# daq.net
KiCad netlist of a schematic drawn in EAGLE
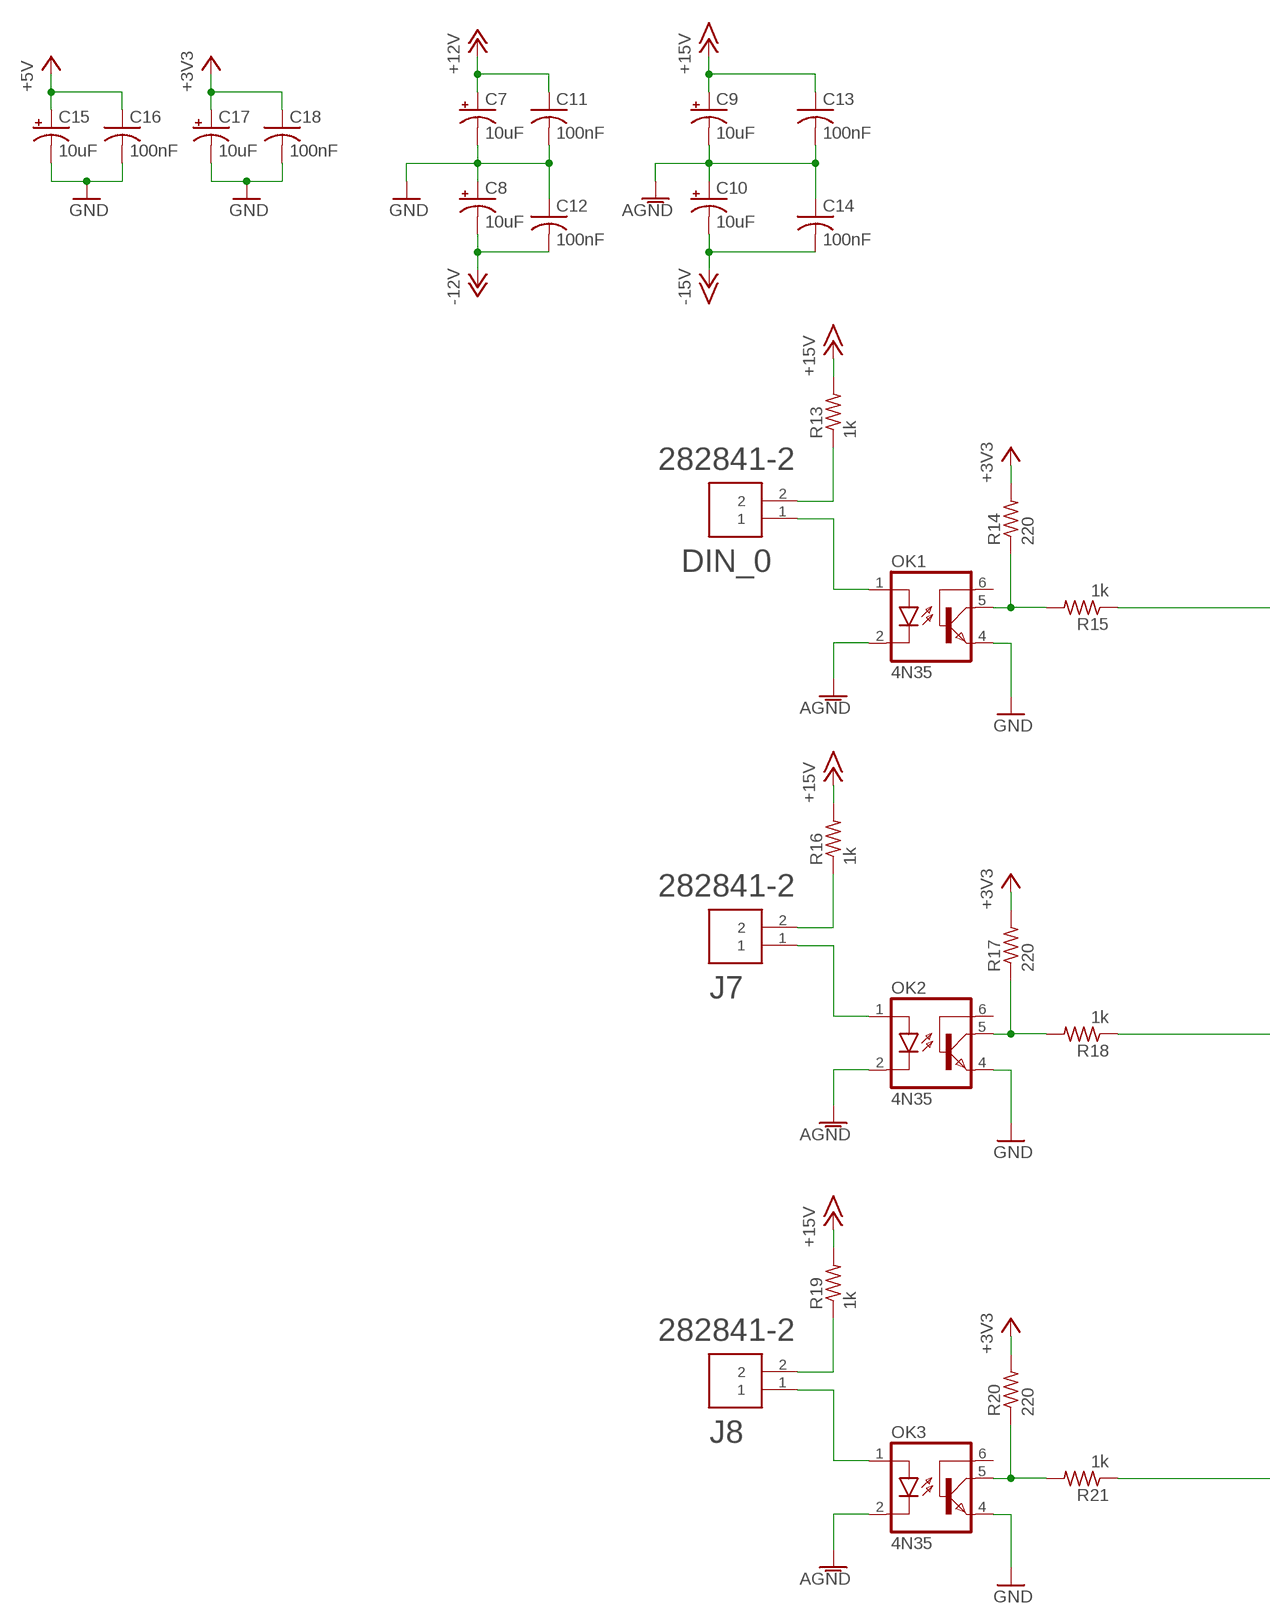
[diagram p0: schematic, sheet 1, part 1 of 2]
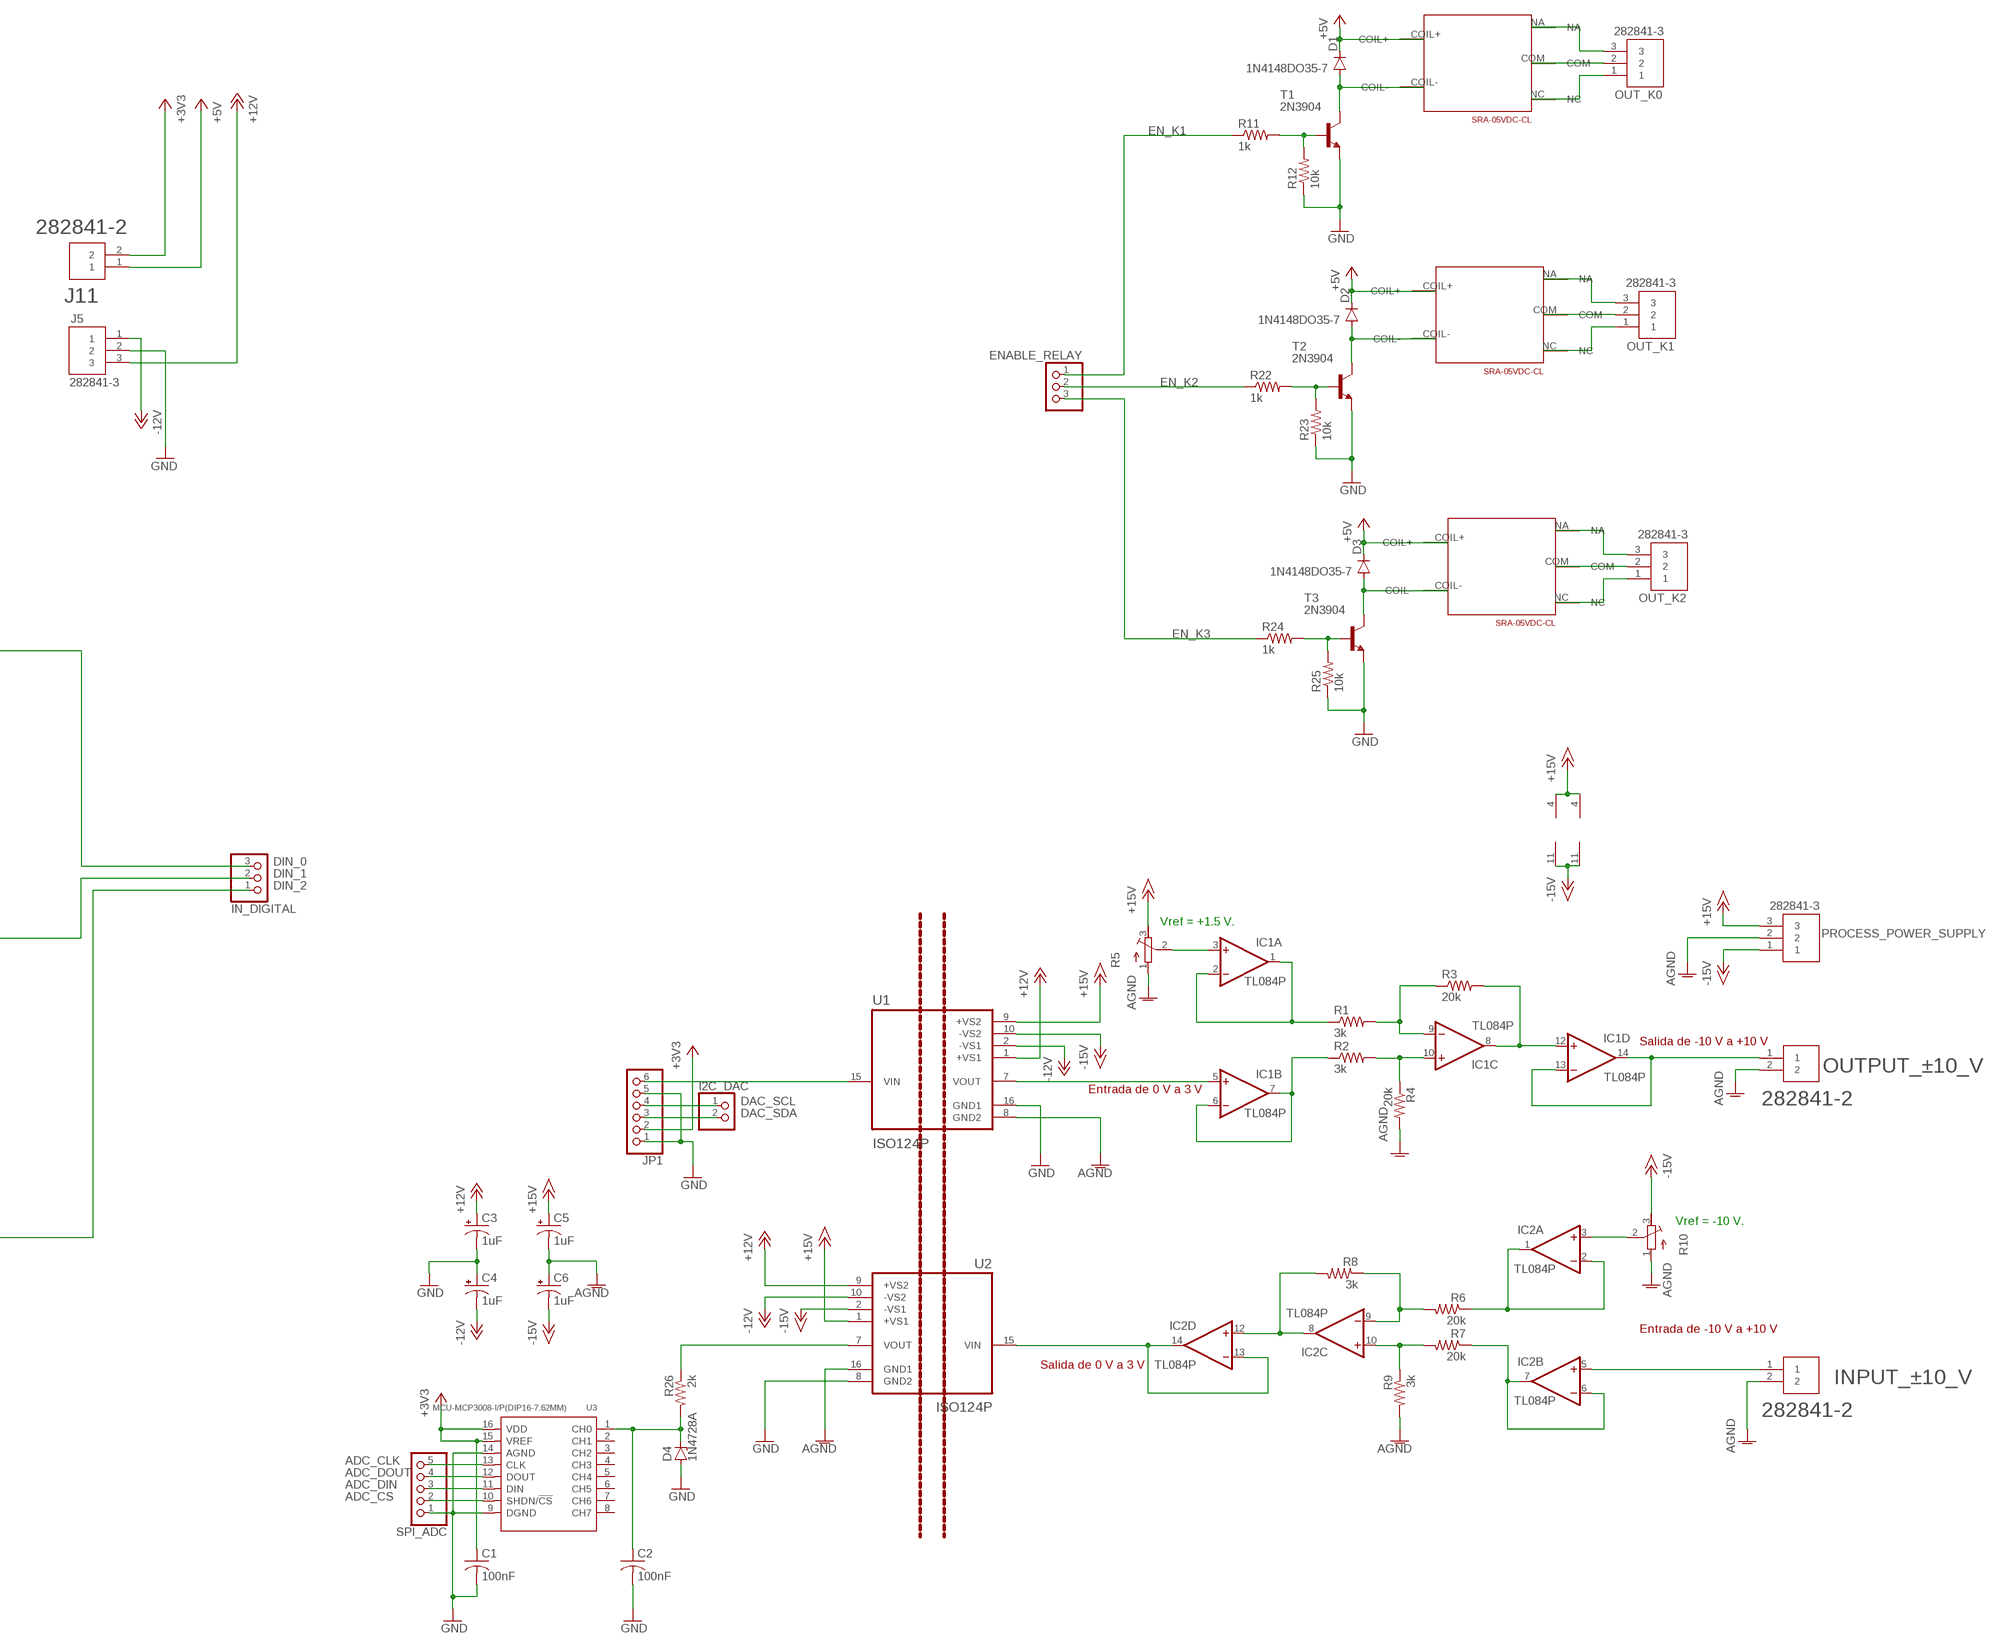
[diagram p1: schematic, sheet 1, part 2 of 2]

(export (version "E")
  (design (tool "Eeschema 10.0.6"))
  (components
    (comp (ref "C1")
      (value "100nF")
      (footprint "eagle-import:C025-025X050")
      (libsource (lib "eagle-import") (part "C-US025-025X050"))
    )
    (comp (ref "C2")
      (value "100nF")
      (footprint "eagle-import:C025-025X050")
      (libsource (lib "eagle-import") (part "C-US025-025X050"))
    )
    (comp (ref "C3")
      (value "1uF")
      (footprint "eagle-import:E2-5")
      (libsource (lib "eagle-import") (part "CPOL-USE2-5"))
    )
    (comp (ref "C4")
      (value "1uF")
      (footprint "eagle-import:E2-5")
      (libsource (lib "eagle-import") (part "CPOL-USE2-5"))
    )
    (comp (ref "C5")
      (value "1uF")
      (footprint "eagle-import:E2-5")
      (libsource (lib "eagle-import") (part "CPOL-USE2-5"))
    )
    (comp (ref "C6")
      (value "1uF")
      (footprint "eagle-import:E2-5")
      (libsource (lib "eagle-import") (part "CPOL-USE2-5"))
    )
    (comp (ref "C7")
      (value "10uF")
      (footprint "eagle-import:E2-5")
      (libsource (lib "eagle-import") (part "CPOL-USE2-5"))
    )
    (comp (ref "C8")
      (value "10uF")
      (footprint "eagle-import:E2-5")
      (libsource (lib "eagle-import") (part "CPOL-USE2-5"))
    )
    (comp (ref "C9")
      (value "10uF")
      (footprint "eagle-import:E2-5")
      (libsource (lib "eagle-import") (part "CPOL-USE2-5"))
    )
    (comp (ref "C10")
      (value "10uF")
      (footprint "eagle-import:E2-5")
      (libsource (lib "eagle-import") (part "CPOL-USE2-5"))
    )
    (comp (ref "C11")
      (value "100nF")
      (footprint "eagle-import:C025-025X050")
      (libsource (lib "eagle-import") (part "C-US025-025X050"))
    )
    (comp (ref "C12")
      (value "100nF")
      (footprint "eagle-import:C025-025X050")
      (libsource (lib "eagle-import") (part "C-US025-025X050"))
    )
    (comp (ref "C13")
      (value "100nF")
      (footprint "eagle-import:C025-025X050")
      (libsource (lib "eagle-import") (part "C-US025-025X050"))
    )
    (comp (ref "C14")
      (value "100nF")
      (footprint "eagle-import:C025-025X050")
      (libsource (lib "eagle-import") (part "C-US025-025X050"))
    )
    (comp (ref "C15")
      (value "10uF")
      (footprint "eagle-import:E2-5")
      (libsource (lib "eagle-import") (part "CPOL-USE2-5"))
    )
    (comp (ref "C16")
      (value "100nF")
      (footprint "eagle-import:C025-025X050")
      (libsource (lib "eagle-import") (part "C-US025-025X050"))
    )
    (comp (ref "C17")
      (value "10uF")
      (footprint "eagle-import:E2-5")
      (libsource (lib "eagle-import") (part "CPOL-USE2-5"))
    )
    (comp (ref "C18")
      (value "100nF")
      (footprint "eagle-import:C025-025X050")
      (libsource (lib "eagle-import") (part "C-US025-025X050"))
    )
    (comp (ref "D1")
      (value "1N4148DO35-7")
      (footprint "eagle-import:DO35-7")
      (libsource (lib "eagle-import") (part "1N4148DO35-7"))
    )
    (comp (ref "D2")
      (value "1N4148DO35-7")
      (footprint "eagle-import:DO35-7")
      (libsource (lib "eagle-import") (part "1N4148DO35-7"))
    )
    (comp (ref "D3")
      (value "1N4148DO35-7")
      (footprint "eagle-import:DO35-7")
      (libsource (lib "eagle-import") (part "1N4148DO35-7"))
    )
    (comp (ref "D4")
      (value "1N4728A")
      (footprint "eagle-import:DO41Z10")
      (libsource (lib "eagle-import") (part "ZENER-DIODEDO41Z10"))
    )
    (comp (ref "DIN_0")
      (value "282841-2")
      (footprint "eagle-import:TE_282841-2")
      (fields (field (name "MF") "TE Connectivity"))
      (libsource (lib "eagle-import") (part "282841-2"))
    )
    (comp (ref "ENABLE_RELAY")
      (value "PINHD-1X3")
      (footprint "eagle-import:1X03")
      (libsource (lib "eagle-import") (part "PINHD-1X3"))
    )
    (comp (ref "I2C_DAC")
      (value "PINHD-1X2")
      (footprint "eagle-import:1X02")
      (libsource (lib "eagle-import") (part "PINHD-1X2"))
    )
    (comp (ref "IC1")
      (value "TL084P")
      (footprint "eagle-import:DIL14")
      (libsource (lib "eagle-import") (part "TL084P"))
    )
    (comp (ref "IC2")
      (value "TL084P")
      (footprint "eagle-import:DIL14")
      (libsource (lib "eagle-import") (part "TL084P"))
    )
    (comp (ref "INPUT_±10_V")
      (value "282841-2")
      (footprint "eagle-import:TE_282841-2")
      (fields (field (name "MF") "TE Connectivity"))
      (libsource (lib "eagle-import") (part "282841-2"))
    )
    (comp (ref "IN_DIGITAL")
      (value "PINHD-1X3")
      (footprint "eagle-import:1X03")
      (libsource (lib "eagle-import") (part "PINHD-1X3"))
    )
    (comp (ref "J5")
      (value "282841-3")
      (footprint "eagle-import:TE_282841-3")
      (fields (field (name "MF") "TE Connectivity"))
      (libsource (lib "eagle-import") (part "282841-3"))
    )
    (comp (ref "J7")
      (value "282841-2")
      (footprint "eagle-import:TE_282841-2")
      (fields (field (name "MF") "TE Connectivity"))
      (libsource (lib "eagle-import") (part "282841-2"))
    )
    (comp (ref "J8")
      (value "282841-2")
      (footprint "eagle-import:TE_282841-2")
      (fields (field (name "MF") "TE Connectivity"))
      (libsource (lib "eagle-import") (part "282841-2"))
    )
    (comp (ref "J11")
      (value "282841-2")
      (footprint "eagle-import:TE_282841-2")
      (fields (field (name "MF") "TE Connectivity"))
      (libsource (lib "eagle-import") (part "282841-2"))
    )
    (comp (ref "JP1")
      (value "PINHD-1X6")
      (footprint "eagle-import:1X06")
      (libsource (lib "eagle-import") (part "PINHD-1X6"))
    )
    (comp (ref "OK1")
      (value "4N35")
      (footprint "eagle-import:DIL06")
      (fields (field (name "MF") "FAIRCHILD SEMICONDUCTOR"))
      (libsource (lib "eagle-import") (part "4N35"))
    )
    (comp (ref "OK2")
      (value "4N35")
      (footprint "eagle-import:DIL06")
      (fields (field (name "MF") "FAIRCHILD SEMICONDUCTOR"))
      (libsource (lib "eagle-import") (part "4N35"))
    )
    (comp (ref "OK3")
      (value "4N35")
      (footprint "eagle-import:DIL06")
      (fields (field (name "MF") "FAIRCHILD SEMICONDUCTOR"))
      (libsource (lib "eagle-import") (part "4N35"))
    )
    (comp (ref "OUTPUT_±10_V")
      (value "282841-2")
      (footprint "eagle-import:TE_282841-2")
      (fields (field (name "MF") "TE Connectivity"))
      (libsource (lib "eagle-import") (part "282841-2"))
    )
    (comp (ref "OUT_K0")
      (value "282841-3")
      (footprint "eagle-import:TE_282841-3")
      (fields (field (name "MF") "TE Connectivity"))
      (libsource (lib "eagle-import") (part "282841-3"))
    )
    (comp (ref "OUT_K1")
      (value "282841-3")
      (footprint "eagle-import:TE_282841-3")
      (fields (field (name "MF") "TE Connectivity"))
      (libsource (lib "eagle-import") (part "282841-3"))
    )
    (comp (ref "OUT_K2")
      (value "282841-3")
      (footprint "eagle-import:TE_282841-3")
      (fields (field (name "MF") "TE Connectivity"))
      (libsource (lib "eagle-import") (part "282841-3"))
    )
    (comp (ref "PROCESS_POWER_SUPPLY")
      (value "282841-3")
      (footprint "eagle-import:TE_282841-3")
      (fields (field (name "MF") "TE Connectivity"))
      (libsource (lib "eagle-import") (part "282841-3"))
    )
    (comp (ref "R1")
      (value "3k")
      (footprint "eagle-import:0207_10")
      (libsource (lib "eagle-import") (part "R-US_0207/10"))
    )
    (comp (ref "R2")
      (value "3k")
      (footprint "eagle-import:0207_10")
      (libsource (lib "eagle-import") (part "R-US_0207/10"))
    )
    (comp (ref "R3")
      (value "20k")
      (footprint "eagle-import:0207_10")
      (libsource (lib "eagle-import") (part "R-US_0207/10"))
    )
    (comp (ref "R4")
      (value "20k")
      (footprint "eagle-import:0207_10")
      (libsource (lib "eagle-import") (part "R-US_0207/10"))
    )
    (comp (ref "R5")
      (value "R-TRIMM64W")
      (footprint "eagle-import:RTRIM64W")
      (libsource (lib "eagle-import") (part "R-TRIMM64W"))
    )
    (comp (ref "R6")
      (value "20k")
      (footprint "eagle-import:0207_10")
      (libsource (lib "eagle-import") (part "R-US_0207/10"))
    )
    (comp (ref "R7")
      (value "20k")
      (footprint "eagle-import:0207_10")
      (libsource (lib "eagle-import") (part "R-US_0207/10"))
    )
    (comp (ref "R8")
      (value "3k")
      (footprint "eagle-import:0207_10")
      (libsource (lib "eagle-import") (part "R-US_0207/10"))
    )
    (comp (ref "R9")
      (value "3k")
      (footprint "eagle-import:0207_10")
      (libsource (lib "eagle-import") (part "R-US_0207/10"))
    )
    (comp (ref "R10")
      (value "R-TRIMM64W")
      (footprint "eagle-import:RTRIM64W")
      (libsource (lib "eagle-import") (part "R-TRIMM64W"))
    )
    (comp (ref "R11")
      (value "1k")
      (footprint "eagle-import:0207_10")
      (libsource (lib "eagle-import") (part "R-US_0207/10"))
    )
    (comp (ref "R12")
      (value "10k")
      (footprint "eagle-import:0207_10")
      (libsource (lib "eagle-import") (part "R-US_0207/10"))
    )
    (comp (ref "R13")
      (value "1k")
      (footprint "eagle-import:0207_10")
      (libsource (lib "eagle-import") (part "R-US_0207/10"))
    )
    (comp (ref "R14")
      (value "220")
      (footprint "eagle-import:0207_10")
      (libsource (lib "eagle-import") (part "R-US_0207/10"))
    )
    (comp (ref "R15")
      (value "1k")
      (footprint "eagle-import:0207_10")
      (libsource (lib "eagle-import") (part "R-US_0207/10"))
    )
    (comp (ref "R16")
      (value "1k")
      (footprint "eagle-import:0207_10")
      (libsource (lib "eagle-import") (part "R-US_0207/10"))
    )
    (comp (ref "R17")
      (value "220")
      (footprint "eagle-import:0207_10")
      (libsource (lib "eagle-import") (part "R-US_0207/10"))
    )
    (comp (ref "R18")
      (value "1k")
      (footprint "eagle-import:0207_10")
      (libsource (lib "eagle-import") (part "R-US_0207/10"))
    )
    (comp (ref "R19")
      (value "1k")
      (footprint "eagle-import:0207_10")
      (libsource (lib "eagle-import") (part "R-US_0207/10"))
    )
    (comp (ref "R20")
      (value "220")
      (footprint "eagle-import:0207_10")
      (libsource (lib "eagle-import") (part "R-US_0207/10"))
    )
    (comp (ref "R21")
      (value "1k")
      (footprint "eagle-import:0207_10")
      (libsource (lib "eagle-import") (part "R-US_0207/10"))
    )
    (comp (ref "R22")
      (value "1k")
      (footprint "eagle-import:0207_10")
      (libsource (lib "eagle-import") (part "R-US_0207/10"))
    )
    (comp (ref "R23")
      (value "10k")
      (footprint "eagle-import:0207_10")
      (libsource (lib "eagle-import") (part "R-US_0207/10"))
    )
    (comp (ref "R24")
      (value "1k")
      (footprint "eagle-import:0207_10")
      (libsource (lib "eagle-import") (part "R-US_0207/10"))
    )
    (comp (ref "R25")
      (value "10k")
      (footprint "eagle-import:0207_10")
      (libsource (lib "eagle-import") (part "R-US_0207/10"))
    )
    (comp (ref "R26")
      (value "2k")
      (footprint "eagle-import:0207_10")
      (libsource (lib "eagle-import") (part "R-US_0207/10"))
    )
    (comp (ref "SPI_ADC")
      (value "PINHD-1X5")
      (footprint "eagle-import:1X05")
      (libsource (lib "eagle-import") (part "PINHD-1X5"))
    )
    (comp (ref "T1")
      (value "2N3904")
      (footprint "eagle-import:TO92")
      (libsource (lib "eagle-import") (part "2N3904"))
    )
    (comp (ref "T2")
      (value "2N3904")
      (footprint "eagle-import:TO92")
      (libsource (lib "eagle-import") (part "2N3904"))
    )
    (comp (ref "T3")
      (value "2N3904")
      (footprint "eagle-import:TO92")
      (libsource (lib "eagle-import") (part "2N3904"))
    )
    (comp (ref "U$1")
      (value "SRA-05VDC-CL")
      (footprint "eagle-import:SRA-05VDC-CL")
      (libsource (lib "eagle-import") (part "SRA-05VDC-CL"))
    )
    (comp (ref "U$2")
      (value "SRA-05VDC-CL")
      (footprint "eagle-import:SRA-05VDC-CL")
      (libsource (lib "eagle-import") (part "SRA-05VDC-CL"))
    )
    (comp (ref "U$3")
      (value "SRA-05VDC-CL")
      (footprint "eagle-import:SRA-05VDC-CL")
      (libsource (lib "eagle-import") (part "SRA-05VDC-CL"))
    )
    (comp (ref "U1")
      (value "ISO124P")
      (footprint "eagle-import:DIP763W46P254L2134H533Q8_16")
      (fields (field (name "MF") "Rochester Electronics, LLC"))
      (libsource (lib "eagle-import") (part "ISO124P"))
    )
    (comp (ref "U2")
      (value "ISO124P")
      (footprint "eagle-import:DIP763W46P254L2134H533Q8_16")
      (fields (field (name "MF") "Rochester Electronics, LLC"))
      (libsource (lib "eagle-import") (part "ISO124P"))
    )
    (comp (ref "U3")
      (value "MCU-MCP3008-I/P(DIP16-7.62MM)")
      (footprint "eagle-import:DIP16-2.54-19.2X7.62MM")
      (fields (field (name "MF") "Microchip Technology") (field (name "MP") "MCP3008-I/P"))
      (libsource (lib "eagle-import") (part "MCU-MCP3008-I/P(DIP16-7.62MM)"))
    )
  )
  (nets
    (net (code "1") (name "+3V3") (class "Default")
      (node (ref "C1") (pin "1") (pinfunction "1_1") (pintype "passive"))
      (node (ref "C17") (pin "+") (pinfunction "+_+") (pintype "passive"))
      (node (ref "C18") (pin "1") (pinfunction "1_1") (pintype "passive"))
      (node (ref "J11") (pin "2") (pinfunction "2_2") (pintype "passive"))
      (node (ref "JP1") (pin "2") (pinfunction "2_2") (pintype "passive"))
      (node (ref "R14") (pin "2") (pinfunction "2_2") (pintype "passive"))
      (node (ref "R17") (pin "2") (pinfunction "2_2") (pintype "passive"))
      (node (ref "R20") (pin "2") (pinfunction "2_2") (pintype "passive"))
      (node (ref "U3") (pin "15") (pinfunction "VREF_15") (pintype "input"))
      (node (ref "U3") (pin "16") (pinfunction "VDD_16") (pintype "power_in"))
    )
    (net (code "2") (name "+5V") (class "Default")
      (node (ref "C15") (pin "+") (pinfunction "+_+") (pintype "passive"))
      (node (ref "C16") (pin "1") (pinfunction "1_1") (pintype "passive"))
      (node (ref "D1") (pin "C") (pinfunction "C_C") (pintype "passive"))
      (node (ref "D2") (pin "C") (pinfunction "C_C") (pintype "passive"))
      (node (ref "D3") (pin "C") (pinfunction "C_C") (pintype "passive"))
      (node (ref "J11") (pin "1") (pinfunction "1_1") (pintype "passive"))
      (node (ref "U$1") (pin "COIL+") (pinfunction "COIL+_COIL+") (pintype "bidirectional"))
      (node (ref "U$2") (pin "COIL+") (pinfunction "COIL+_COIL+") (pintype "bidirectional"))
      (node (ref "U$3") (pin "COIL+") (pinfunction "COIL+_COIL+") (pintype "bidirectional"))
    )
    (net (code "3") (name "+12V") (class "Default")
      (node (ref "C11") (pin "1") (pinfunction "1_1") (pintype "passive"))
      (node (ref "C3") (pin "+") (pinfunction "+_+") (pintype "passive"))
      (node (ref "C7") (pin "+") (pinfunction "+_+") (pintype "passive"))
      (node (ref "J5") (pin "3") (pinfunction "3_3") (pintype "passive"))
      (node (ref "U1") (pin "1") (pinfunction "+VS1_1") (pintype "power_in"))
      (node (ref "U2") (pin "9") (pinfunction "+VS2_9") (pintype "power_in"))
    )
    (net (code "4") (name "+15V") (class "Default")
      (node (ref "C13") (pin "1") (pinfunction "1_1") (pintype "passive"))
      (node (ref "C5") (pin "+") (pinfunction "+_+") (pintype "passive"))
      (node (ref "C9") (pin "+") (pinfunction "+_+") (pintype "passive"))
      (node (ref "IC1") (pin "4") (pinfunction "V+_4") (pintype "power_in"))
      (node (ref "IC2") (pin "4") (pinfunction "V+_4") (pintype "power_in"))
      (node (ref "PROCESS_POWER_SUPPLY") (pin "3") (pinfunction "3_3") (pintype "passive"))
      (node (ref "R13") (pin "2") (pinfunction "2_2") (pintype "passive"))
      (node (ref "R16") (pin "2") (pinfunction "2_2") (pintype "passive"))
      (node (ref "R19") (pin "2") (pinfunction "2_2") (pintype "passive"))
      (node (ref "R5") (pin "3") (pinfunction "E_3") (pintype "passive"))
      (node (ref "U1") (pin "9") (pinfunction "+VS2_9") (pintype "power_in"))
      (node (ref "U2") (pin "1") (pinfunction "+VS1_1") (pintype "power_in"))
    )
    (net (code "5") (name "-12V") (class "Default")
      (node (ref "C12") (pin "2") (pinfunction "2_2") (pintype "passive"))
      (node (ref "C4") (pin "-") (pinfunction "-_-") (pintype "passive"))
      (node (ref "C8") (pin "-") (pinfunction "-_-") (pintype "passive"))
      (node (ref "J5") (pin "1") (pinfunction "1_1") (pintype "passive"))
      (node (ref "U1") (pin "2") (pinfunction "-VS1_2") (pintype "power_in"))
      (node (ref "U2") (pin "10") (pinfunction "-VS2_10") (pintype "power_in"))
    )
    (net (code "6") (name "-15V") (class "Default")
      (node (ref "C10") (pin "-") (pinfunction "-_-") (pintype "passive"))
      (node (ref "C14") (pin "2") (pinfunction "2_2") (pintype "passive"))
      (node (ref "C6") (pin "-") (pinfunction "-_-") (pintype "passive"))
      (node (ref "IC1") (pin "11") (pinfunction "V-_11") (pintype "power_in"))
      (node (ref "IC2") (pin "11") (pinfunction "V-_11") (pintype "power_in"))
      (node (ref "PROCESS_POWER_SUPPLY") (pin "1") (pinfunction "1_1") (pintype "passive"))
      (node (ref "R10") (pin "3") (pinfunction "E_3") (pintype "passive"))
      (node (ref "U1") (pin "10") (pinfunction "-VS2_10") (pintype "power_in"))
      (node (ref "U2") (pin "2") (pinfunction "-VS1_2") (pintype "power_in"))
    )
    (net (code "7") (name "/ADC_CLK") (class "Default")
      (node (ref "SPI_ADC") (pin "5") (pinfunction "5_5") (pintype "passive"))
      (node (ref "U3") (pin "13") (pinfunction "CLK_13") (pintype "output"))
    )
    (net (code "8") (name "/ADC_CS") (class "Default")
      (node (ref "SPI_ADC") (pin "2") (pinfunction "2_2") (pintype "passive"))
      (node (ref "U3") (pin "10") (pinfunction "SHDN/~{CS}_10") (pintype "output"))
    )
    (net (code "9") (name "/ADC_DIN") (class "Default")
      (node (ref "SPI_ADC") (pin "3") (pinfunction "3_3") (pintype "passive"))
      (node (ref "U3") (pin "11") (pinfunction "DIN_11") (pintype "input"))
    )
    (net (code "10") (name "/ADC_DOUT") (class "Default")
      (node (ref "SPI_ADC") (pin "4") (pinfunction "4_4") (pintype "passive"))
      (node (ref "U3") (pin "12") (pinfunction "DOUT_12") (pintype "input"))
    )
    (net (code "11") (name "/DAC_SCL") (class "Default")
      (node (ref "I2C_DAC") (pin "1") (pinfunction "1_1") (pintype "passive"))
      (node (ref "JP1") (pin "4") (pinfunction "4_4") (pintype "passive"))
    )
    (net (code "12") (name "/DAC_SDA") (class "Default")
      (node (ref "I2C_DAC") (pin "2") (pinfunction "2_2") (pintype "passive"))
      (node (ref "JP1") (pin "3") (pinfunction "3_3") (pintype "passive"))
    )
    (net (code "13") (name "/DIN_0") (class "Default")
      (node (ref "IN_DIGITAL") (pin "3") (pinfunction "3_3") (pintype "passive"))
      (node (ref "R15") (pin "1") (pinfunction "1_1") (pintype "passive"))
    )
    (net (code "14") (name "/DIN_1") (class "Default")
      (node (ref "IN_DIGITAL") (pin "2") (pinfunction "2_2") (pintype "passive"))
      (node (ref "R18") (pin "1") (pinfunction "1_1") (pintype "passive"))
    )
    (net (code "15") (name "/DIN_2") (class "Default")
      (node (ref "IN_DIGITAL") (pin "1") (pinfunction "1_1") (pintype "passive"))
      (node (ref "R21") (pin "1") (pinfunction "1_1") (pintype "passive"))
    )
    (net (code "16") (name "/EN_K1") (class "Default")
      (node (ref "ENABLE_RELAY") (pin "1") (pinfunction "1_1") (pintype "passive"))
      (node (ref "R11") (pin "1") (pinfunction "1_1") (pintype "passive"))
    )
    (net (code "17") (name "/EN_K2") (class "Default")
      (node (ref "ENABLE_RELAY") (pin "2") (pinfunction "2_2") (pintype "passive"))
      (node (ref "R22") (pin "1") (pinfunction "1_1") (pintype "passive"))
    )
    (net (code "18") (name "/EN_K3") (class "Default")
      (node (ref "ENABLE_RELAY") (pin "3") (pinfunction "3_3") (pintype "passive"))
      (node (ref "R24") (pin "1") (pinfunction "1_1") (pintype "passive"))
    )
    (net (code "19") (name "AGND") (class "Default")
      (node (ref "C10") (pin "+") (pinfunction "+_+") (pintype "passive"))
      (node (ref "C13") (pin "2") (pinfunction "2_2") (pintype "passive"))
      (node (ref "C14") (pin "1") (pinfunction "1_1") (pintype "passive"))
      (node (ref "C5") (pin "-") (pinfunction "-_-") (pintype "passive"))
      (node (ref "C6") (pin "+") (pinfunction "+_+") (pintype "passive"))
      (node (ref "C9") (pin "-") (pinfunction "-_-") (pintype "passive"))
      (node (ref "INPUT_±10_V") (pin "2") (pinfunction "2_2") (pintype "passive"))
      (node (ref "OK1") (pin "2") (pinfunction "C_2") (pintype "passive"))
      (node (ref "OK2") (pin "2") (pinfunction "C_2") (pintype "passive"))
      (node (ref "OK3") (pin "2") (pinfunction "C_2") (pintype "passive"))
      (node (ref "OUTPUT_±10_V") (pin "2") (pinfunction "2_2") (pintype "passive"))
      (node (ref "PROCESS_POWER_SUPPLY") (pin "2") (pinfunction "2_2") (pintype "passive"))
      (node (ref "R10") (pin "1") (pinfunction "A_1") (pintype "passive"))
      (node (ref "R4") (pin "2") (pinfunction "2_2") (pintype "passive"))
      (node (ref "R5") (pin "1") (pinfunction "A_1") (pintype "passive"))
      (node (ref "R9") (pin "2") (pinfunction "2_2") (pintype "passive"))
      (node (ref "U1") (pin "8") (pinfunction "GND2_8") (pintype "power_in"))
      (node (ref "U2") (pin "16") (pinfunction "GND1_16") (pintype "power_in"))
    )
    (net (code "20") (name "GND") (class "Default")
      (node (ref "C1") (pin "2") (pinfunction "2_2") (pintype "passive"))
      (node (ref "C11") (pin "2") (pinfunction "2_2") (pintype "passive"))
      (node (ref "C12") (pin "1") (pinfunction "1_1") (pintype "passive"))
      (node (ref "C15") (pin "-") (pinfunction "-_-") (pintype "passive"))
      (node (ref "C16") (pin "2") (pinfunction "2_2") (pintype "passive"))
      (node (ref "C17") (pin "-") (pinfunction "-_-") (pintype "passive"))
      (node (ref "C18") (pin "2") (pinfunction "2_2") (pintype "passive"))
      (node (ref "C2") (pin "2") (pinfunction "2_2") (pintype "passive"))
      (node (ref "C3") (pin "-") (pinfunction "-_-") (pintype "passive"))
      (node (ref "C4") (pin "+") (pinfunction "+_+") (pintype "passive"))
      (node (ref "C7") (pin "-") (pinfunction "-_-") (pintype "passive"))
      (node (ref "C8") (pin "+") (pinfunction "+_+") (pintype "passive"))
      (node (ref "D4") (pin "A") (pinfunction "A_A") (pintype "passive"))
      (node (ref "J5") (pin "2") (pinfunction "2_2") (pintype "passive"))
      (node (ref "JP1") (pin "1") (pinfunction "1_1") (pintype "passive"))
      (node (ref "JP1") (pin "5") (pinfunction "5_5") (pintype "passive"))
      (node (ref "OK1") (pin "4") (pinfunction "EMI_4") (pintype "passive"))
      (node (ref "OK2") (pin "4") (pinfunction "EMI_4") (pintype "passive"))
      (node (ref "OK3") (pin "4") (pinfunction "EMI_4") (pintype "passive"))
      (node (ref "R12") (pin "1") (pinfunction "1_1") (pintype "passive"))
      (node (ref "R23") (pin "1") (pinfunction "1_1") (pintype "passive"))
      (node (ref "R25") (pin "1") (pinfunction "1_1") (pintype "passive"))
      (node (ref "SPI_ADC") (pin "1") (pinfunction "1_1") (pintype "passive"))
      (node (ref "T1") (pin "3") (pinfunction "E_3") (pintype "passive"))
      (node (ref "T2") (pin "3") (pinfunction "E_3") (pintype "passive"))
      (node (ref "T3") (pin "3") (pinfunction "E_3") (pintype "passive"))
      (node (ref "U1") (pin "16") (pinfunction "GND1_16") (pintype "power_in"))
      (node (ref "U2") (pin "8") (pinfunction "GND2_8") (pintype "power_in"))
      (node (ref "U3") (pin "14") (pinfunction "AGND_14") (pintype "input"))
      (node (ref "U3") (pin "9") (pinfunction "DGND_9") (pintype "output"))
    )
    (net (code "21") (name "Net-(DIN_0-Pad2)") (class "Default")
      (node (ref "DIN_0") (pin "2") (pinfunction "2_2") (pintype "passive"))
      (node (ref "R13") (pin "1") (pinfunction "1_1") (pintype "passive"))
    )
    (net (code "22") (name "Net-(IC1A-+IN)") (class "Default")
      (node (ref "IC1") (pin "3") (pinfunction "+IN_3") (pintype "input"))
      (node (ref "R5") (pin "2") (pinfunction "S_2") (pintype "passive"))
    )
    (net (code "23") (name "Net-(IC1A--IN)") (class "Default")
      (node (ref "IC1") (pin "1") (pinfunction "OUT_1") (pintype "output"))
      (node (ref "IC1") (pin "2") (pinfunction "-IN_2") (pintype "input"))
      (node (ref "R1") (pin "1") (pinfunction "1_1") (pintype "passive"))
    )
    (net (code "24") (name "Net-(IC1B-+IN)") (class "Default")
      (node (ref "IC1") (pin "5") (pinfunction "+IN_5") (pintype "input"))
      (node (ref "U1") (pin "7") (pinfunction "VOUT_7") (pintype "output"))
    )
    (net (code "25") (name "Net-(IC1B--IN)") (class "Default")
      (node (ref "IC1") (pin "6") (pinfunction "-IN_6") (pintype "input"))
      (node (ref "IC1") (pin "7") (pinfunction "OUT_7") (pintype "output"))
      (node (ref "R2") (pin "1") (pinfunction "1_1") (pintype "passive"))
    )
    (net (code "26") (name "Net-(IC1C-+IN)") (class "Default")
      (node (ref "IC1") (pin "10") (pinfunction "+IN_10") (pintype "input"))
      (node (ref "R2") (pin "2") (pinfunction "2_2") (pintype "passive"))
      (node (ref "R4") (pin "1") (pinfunction "1_1") (pintype "passive"))
    )
    (net (code "27") (name "Net-(IC1C--IN)") (class "Default")
      (node (ref "IC1") (pin "9") (pinfunction "-IN_9") (pintype "input"))
      (node (ref "R1") (pin "2") (pinfunction "2_2") (pintype "passive"))
      (node (ref "R3") (pin "1") (pinfunction "1_1") (pintype "passive"))
    )
    (net (code "28") (name "Net-(IC1C-OUT)") (class "Default")
      (node (ref "IC1") (pin "12") (pinfunction "+IN_12") (pintype "input"))
      (node (ref "IC1") (pin "8") (pinfunction "OUT_8") (pintype "output"))
      (node (ref "R3") (pin "2") (pinfunction "2_2") (pintype "passive"))
    )
    (net (code "29") (name "Net-(IC1D--IN)") (class "Default")
      (node (ref "IC1") (pin "13") (pinfunction "-IN_13") (pintype "input"))
      (node (ref "IC1") (pin "14") (pinfunction "OUT_14") (pintype "output"))
      (node (ref "OUTPUT_±10_V") (pin "1") (pinfunction "1_1") (pintype "passive"))
    )
    (net (code "30") (name "Net-(IC2A-+IN)") (class "Default")
      (node (ref "IC2") (pin "3") (pinfunction "+IN_3") (pintype "input"))
      (node (ref "R10") (pin "2") (pinfunction "S_2") (pintype "passive"))
    )
    (net (code "31") (name "Net-(IC2A--IN)") (class "Default")
      (node (ref "IC2") (pin "1") (pinfunction "OUT_1") (pintype "output"))
      (node (ref "IC2") (pin "2") (pinfunction "-IN_2") (pintype "input"))
      (node (ref "R6") (pin "1") (pinfunction "1_1") (pintype "passive"))
    )
    (net (code "32") (name "Net-(IC2B-+IN)") (class "Default")
      (node (ref "IC2") (pin "5") (pinfunction "+IN_5") (pintype "input"))
      (node (ref "INPUT_±10_V") (pin "1") (pinfunction "1_1") (pintype "passive"))
    )
    (net (code "33") (name "Net-(IC2B--IN)") (class "Default")
      (node (ref "IC2") (pin "6") (pinfunction "-IN_6") (pintype "input"))
      (node (ref "IC2") (pin "7") (pinfunction "OUT_7") (pintype "output"))
      (node (ref "R7") (pin "1") (pinfunction "1_1") (pintype "passive"))
    )
    (net (code "34") (name "Net-(IC2C-+IN)") (class "Default")
      (node (ref "IC2") (pin "10") (pinfunction "+IN_10") (pintype "input"))
      (node (ref "R7") (pin "2") (pinfunction "2_2") (pintype "passive"))
      (node (ref "R9") (pin "1") (pinfunction "1_1") (pintype "passive"))
    )
    (net (code "35") (name "Net-(IC2C--IN)") (class "Default")
      (node (ref "IC2") (pin "9") (pinfunction "-IN_9") (pintype "input"))
      (node (ref "R6") (pin "2") (pinfunction "2_2") (pintype "passive"))
      (node (ref "R8") (pin "1") (pinfunction "1_1") (pintype "passive"))
    )
    (net (code "36") (name "Net-(IC2C-OUT)") (class "Default")
      (node (ref "IC2") (pin "12") (pinfunction "+IN_12") (pintype "input"))
      (node (ref "IC2") (pin "8") (pinfunction "OUT_8") (pintype "output"))
      (node (ref "R8") (pin "2") (pinfunction "2_2") (pintype "passive"))
    )
    (net (code "37") (name "Net-(IC2D--IN)") (class "Default")
      (node (ref "IC2") (pin "13") (pinfunction "-IN_13") (pintype "input"))
      (node (ref "IC2") (pin "14") (pinfunction "OUT_14") (pintype "output"))
      (node (ref "U2") (pin "15") (pinfunction "VIN_15") (pintype "input"))
    )
    (net (code "38") (name "Net-(J7-Pad2)") (class "Default")
      (node (ref "J7") (pin "2") (pinfunction "2_2") (pintype "passive"))
      (node (ref "R16") (pin "1") (pinfunction "1_1") (pintype "passive"))
    )
    (net (code "39") (name "Net-(J8-Pad2)") (class "Default")
      (node (ref "J8") (pin "2") (pinfunction "2_2") (pintype "passive"))
      (node (ref "R19") (pin "1") (pinfunction "1_1") (pintype "passive"))
    )
    (net (code "40") (name "Net-(OK1-A)") (class "Default")
      (node (ref "DIN_0") (pin "1") (pinfunction "1_1") (pintype "passive"))
      (node (ref "OK1") (pin "1") (pinfunction "A_1") (pintype "passive"))
    )
    (net (code "41") (name "Net-(OK1-COL)") (class "Default")
      (node (ref "OK1") (pin "5") (pinfunction "COL_5") (pintype "passive"))
      (node (ref "R14") (pin "1") (pinfunction "1_1") (pintype "passive"))
      (node (ref "R15") (pin "2") (pinfunction "2_2") (pintype "passive"))
    )
    (net (code "42") (name "Net-(OK2-A)") (class "Default")
      (node (ref "J7") (pin "1") (pinfunction "1_1") (pintype "passive"))
      (node (ref "OK2") (pin "1") (pinfunction "A_1") (pintype "passive"))
    )
    (net (code "43") (name "Net-(OK2-COL)") (class "Default")
      (node (ref "OK2") (pin "5") (pinfunction "COL_5") (pintype "passive"))
      (node (ref "R17") (pin "1") (pinfunction "1_1") (pintype "passive"))
      (node (ref "R18") (pin "2") (pinfunction "2_2") (pintype "passive"))
    )
    (net (code "44") (name "Net-(OK3-A)") (class "Default")
      (node (ref "J8") (pin "1") (pinfunction "1_1") (pintype "passive"))
      (node (ref "OK3") (pin "1") (pinfunction "A_1") (pintype "passive"))
    )
    (net (code "45") (name "Net-(OK3-COL)") (class "Default")
      (node (ref "OK3") (pin "5") (pinfunction "COL_5") (pintype "passive"))
      (node (ref "R20") (pin "1") (pinfunction "1_1") (pintype "passive"))
      (node (ref "R21") (pin "2") (pinfunction "2_2") (pintype "passive"))
    )
    (net (code "46") (name "Net-(OUT_K0-Pad1)") (class "Default")
      (node (ref "OUT_K0") (pin "1") (pinfunction "1_1") (pintype "passive"))
      (node (ref "U$1") (pin "NC") (pinfunction "NC_NC") (pintype "bidirectional"))
    )
    (net (code "47") (name "Net-(OUT_K0-Pad2)") (class "Default")
      (node (ref "OUT_K0") (pin "2") (pinfunction "2_2") (pintype "passive"))
      (node (ref "U$1") (pin "COM") (pinfunction "COM_COM") (pintype "bidirectional"))
    )
    (net (code "48") (name "Net-(OUT_K0-Pad3)") (class "Default")
      (node (ref "OUT_K0") (pin "3") (pinfunction "3_3") (pintype "passive"))
      (node (ref "U$1") (pin "NA") (pinfunction "NA_NA") (pintype "bidirectional"))
    )
    (net (code "49") (name "Net-(OUT_K1-Pad1)") (class "Default")
      (node (ref "OUT_K1") (pin "1") (pinfunction "1_1") (pintype "passive"))
      (node (ref "U$2") (pin "NC") (pinfunction "NC_NC") (pintype "bidirectional"))
    )
    (net (code "50") (name "Net-(OUT_K1-Pad2)") (class "Default")
      (node (ref "OUT_K1") (pin "2") (pinfunction "2_2") (pintype "passive"))
      (node (ref "U$2") (pin "COM") (pinfunction "COM_COM") (pintype "bidirectional"))
    )
    (net (code "51") (name "Net-(OUT_K1-Pad3)") (class "Default")
      (node (ref "OUT_K1") (pin "3") (pinfunction "3_3") (pintype "passive"))
      (node (ref "U$2") (pin "NA") (pinfunction "NA_NA") (pintype "bidirectional"))
    )
    (net (code "52") (name "Net-(OUT_K2-Pad1)") (class "Default")
      (node (ref "OUT_K2") (pin "1") (pinfunction "1_1") (pintype "passive"))
      (node (ref "U$3") (pin "NC") (pinfunction "NC_NC") (pintype "bidirectional"))
    )
    (net (code "53") (name "Net-(OUT_K2-Pad2)") (class "Default")
      (node (ref "OUT_K2") (pin "2") (pinfunction "2_2") (pintype "passive"))
      (node (ref "U$3") (pin "COM") (pinfunction "COM_COM") (pintype "bidirectional"))
    )
    (net (code "54") (name "Net-(OUT_K2-Pad3)") (class "Default")
      (node (ref "OUT_K2") (pin "3") (pinfunction "3_3") (pintype "passive"))
      (node (ref "U$3") (pin "NA") (pinfunction "NA_NA") (pintype "bidirectional"))
    )
    (net (code "55") (name "Net-(T1-B)") (class "Default")
      (node (ref "R11") (pin "2") (pinfunction "2_2") (pintype "passive"))
      (node (ref "R12") (pin "2") (pinfunction "2_2") (pintype "passive"))
      (node (ref "T1") (pin "2") (pinfunction "B_2") (pintype "passive"))
    )
    (net (code "56") (name "Net-(T1-C)") (class "Default")
      (node (ref "D1") (pin "A") (pinfunction "A_A") (pintype "passive"))
      (node (ref "T1") (pin "1") (pinfunction "C_1") (pintype "passive"))
      (node (ref "U$1") (pin "COIL-") (pinfunction "COIL-_COIL-") (pintype "bidirectional"))
    )
    (net (code "57") (name "Net-(T2-B)") (class "Default")
      (node (ref "R22") (pin "2") (pinfunction "2_2") (pintype "passive"))
      (node (ref "R23") (pin "2") (pinfunction "2_2") (pintype "passive"))
      (node (ref "T2") (pin "2") (pinfunction "B_2") (pintype "passive"))
    )
    (net (code "58") (name "Net-(T2-C)") (class "Default")
      (node (ref "D2") (pin "A") (pinfunction "A_A") (pintype "passive"))
      (node (ref "T2") (pin "1") (pinfunction "C_1") (pintype "passive"))
      (node (ref "U$2") (pin "COIL-") (pinfunction "COIL-_COIL-") (pintype "bidirectional"))
    )
    (net (code "59") (name "Net-(T3-B)") (class "Default")
      (node (ref "R24") (pin "2") (pinfunction "2_2") (pintype "passive"))
      (node (ref "R25") (pin "2") (pinfunction "2_2") (pintype "passive"))
      (node (ref "T3") (pin "2") (pinfunction "B_2") (pintype "passive"))
    )
    (net (code "60") (name "Net-(T3-C)") (class "Default")
      (node (ref "D3") (pin "A") (pinfunction "A_A") (pintype "passive"))
      (node (ref "T3") (pin "1") (pinfunction "C_1") (pintype "passive"))
      (node (ref "U$3") (pin "COIL-") (pinfunction "COIL-_COIL-") (pintype "bidirectional"))
    )
    (net (code "61") (name "Net-(U1-VIN)") (class "Default")
      (node (ref "JP1") (pin "6") (pinfunction "6_6") (pintype "passive"))
      (node (ref "U1") (pin "15") (pinfunction "VIN_15") (pintype "input"))
    )
    (net (code "62") (name "Net-(U2-VOUT)") (class "Default")
      (node (ref "R26") (pin "1") (pinfunction "1_1") (pintype "passive"))
      (node (ref "U2") (pin "7") (pinfunction "VOUT_7") (pintype "output"))
    )
    (net (code "63") (name "Net-(U3-CH0)") (class "Default")
      (node (ref "C2") (pin "1") (pinfunction "1_1") (pintype "passive"))
      (node (ref "D4") (pin "C") (pinfunction "C_C") (pintype "passive"))
      (node (ref "R26") (pin "2") (pinfunction "2_2") (pintype "passive"))
      (node (ref "U3") (pin "1") (pinfunction "CH0_1") (pintype "output"))
    )
    (net (code "64") (name "unconnected-(OK1-BAS-Pad6)") (class "Default")
      (node (ref "OK1") (pin "6") (pinfunction "BAS_6") (pintype "passive"))
    )
    (net (code "65") (name "unconnected-(OK2-BAS-Pad6)") (class "Default")
      (node (ref "OK2") (pin "6") (pinfunction "BAS_6") (pintype "passive"))
    )
    (net (code "66") (name "unconnected-(OK3-BAS-Pad6)") (class "Default")
      (node (ref "OK3") (pin "6") (pinfunction "BAS_6") (pintype "passive"))
    )
    (net (code "67") (name "unconnected-(U3-CH1-Pad2)") (class "Default")
      (node (ref "U3") (pin "2") (pinfunction "CH1_2") (pintype "input"))
    )
    (net (code "68") (name "unconnected-(U3-CH2-Pad3)") (class "Default")
      (node (ref "U3") (pin "3") (pinfunction "CH2_3") (pintype "output"))
    )
    (net (code "69") (name "unconnected-(U3-CH3-Pad4)") (class "Default")
      (node (ref "U3") (pin "4") (pinfunction "CH3_4") (pintype "input"))
    )
    (net (code "70") (name "unconnected-(U3-CH4-Pad5)") (class "Default")
      (node (ref "U3") (pin "5") (pinfunction "CH4_5") (pintype "input"))
    )
    (net (code "71") (name "unconnected-(U3-CH5-Pad6)") (class "Default")
      (node (ref "U3") (pin "6") (pinfunction "CH5_6") (pintype "input"))
    )
    (net (code "72") (name "unconnected-(U3-CH6-Pad7)") (class "Default")
      (node (ref "U3") (pin "7") (pinfunction "CH6_7") (pintype "output"))
    )
    (net (code "73") (name "unconnected-(U3-CH7-Pad8)") (class "Default")
      (node (ref "U3") (pin "8") (pinfunction "CH7_8") (pintype "input"))
    )
  )
)
